# buffer.net
KiCad netlist of a schematic drawn in EAGLE
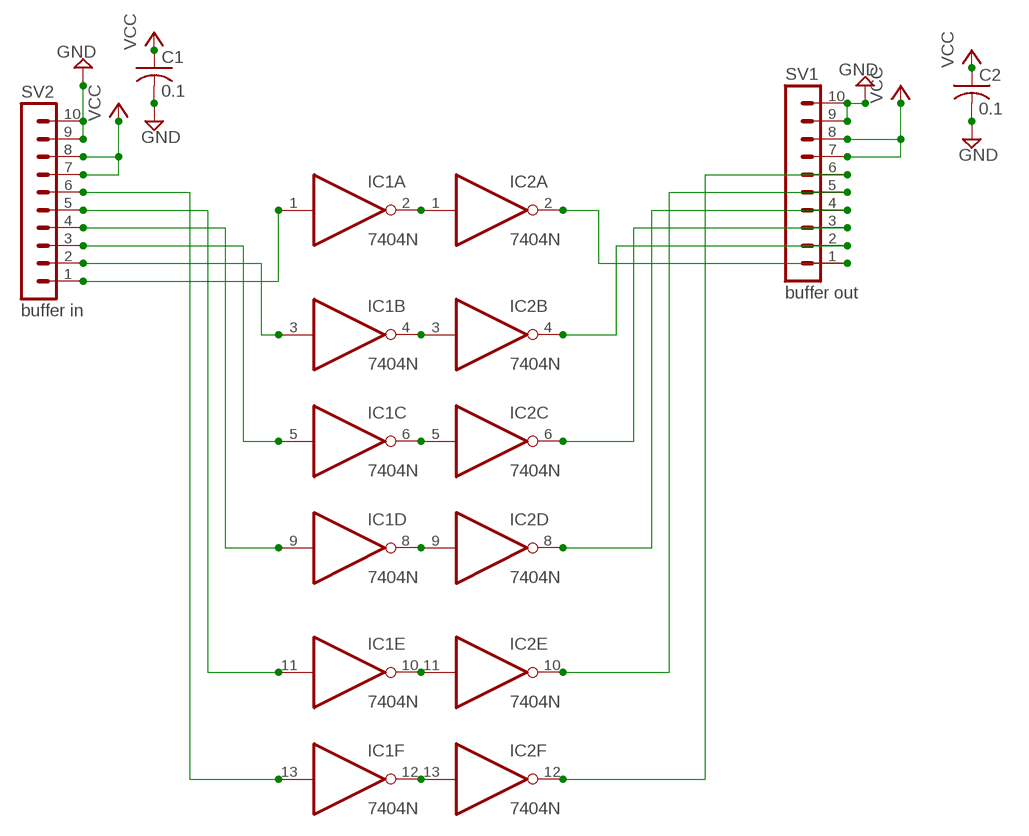
[diagram p0: schematic, sheet 1]

(export (version "E")
  (design (tool "Eeschema 10.0.6"))
  (components
    (comp (ref "C1")
      (value "0.1")
      (footprint "eagle-import:C1206")
      (libsource (lib "eagle-import") (part "C-USC1206"))
    )
    (comp (ref "C2")
      (value "0.1")
      (footprint "eagle-import:C1206")
      (libsource (lib "eagle-import") (part "C-USC1206"))
    )
    (comp (ref "IC1")
      (value "7404N")
      (footprint "eagle-import:DIL14")
      (libsource (lib "eagle-import") (part "7404N"))
    )
    (comp (ref "IC2")
      (value "7404N")
      (footprint "eagle-import:DIL14")
      (libsource (lib "eagle-import") (part "7404N"))
    )
    (comp (ref "SV1")
      (value "buffer out")
      (footprint "eagle-import:MA10-1")
      (libsource (lib "eagle-import") (part "MA10-1"))
    )
    (comp (ref "SV2")
      (value "buffer in")
      (footprint "eagle-import:MA10-1")
      (libsource (lib "eagle-import") (part "MA10-1"))
    )
  )
  (nets
    (net (code "1") (name "GND") (class "Default")
      (node (ref "C1") (pin "2") (pinfunction "2_2") (pintype "passive"))
      (node (ref "C2") (pin "2") (pinfunction "2_2") (pintype "passive"))
      (node (ref "SV1") (pin "10") (pinfunction "10_10") (pintype "passive"))
      (node (ref "SV1") (pin "9") (pinfunction "9_9") (pintype "passive"))
      (node (ref "SV2") (pin "10") (pinfunction "10_10") (pintype "passive"))
      (node (ref "SV2") (pin "9") (pinfunction "9_9") (pintype "passive"))
    )
    (net (code "2") (name "Net-(IC1A-I)") (class "Default")
      (node (ref "IC1") (pin "1") (pinfunction "I_1") (pintype "input"))
      (node (ref "SV2") (pin "1") (pinfunction "1_1") (pintype "passive"))
    )
    (net (code "3") (name "Net-(IC1A-O)") (class "Default")
      (node (ref "IC1") (pin "2") (pinfunction "O_2") (pintype "output"))
      (node (ref "IC2") (pin "1") (pinfunction "I_1") (pintype "input"))
    )
    (net (code "4") (name "Net-(IC1B-I)") (class "Default")
      (node (ref "IC1") (pin "3") (pinfunction "I_3") (pintype "input"))
      (node (ref "SV2") (pin "2") (pinfunction "2_2") (pintype "passive"))
    )
    (net (code "5") (name "Net-(IC1B-O)") (class "Default")
      (node (ref "IC1") (pin "4") (pinfunction "O_4") (pintype "output"))
      (node (ref "IC2") (pin "3") (pinfunction "I_3") (pintype "input"))
    )
    (net (code "6") (name "Net-(IC1C-I)") (class "Default")
      (node (ref "IC1") (pin "5") (pinfunction "I_5") (pintype "input"))
      (node (ref "SV2") (pin "3") (pinfunction "3_3") (pintype "passive"))
    )
    (net (code "7") (name "Net-(IC1C-O)") (class "Default")
      (node (ref "IC1") (pin "6") (pinfunction "O_6") (pintype "output"))
      (node (ref "IC2") (pin "5") (pinfunction "I_5") (pintype "input"))
    )
    (net (code "8") (name "Net-(IC1D-I)") (class "Default")
      (node (ref "IC1") (pin "9") (pinfunction "I_9") (pintype "input"))
      (node (ref "SV2") (pin "4") (pinfunction "4_4") (pintype "passive"))
    )
    (net (code "9") (name "Net-(IC1D-O)") (class "Default")
      (node (ref "IC1") (pin "8") (pinfunction "O_8") (pintype "output"))
      (node (ref "IC2") (pin "9") (pinfunction "I_9") (pintype "input"))
    )
    (net (code "10") (name "Net-(IC1E-I)") (class "Default")
      (node (ref "IC1") (pin "11") (pinfunction "I_11") (pintype "input"))
      (node (ref "SV2") (pin "5") (pinfunction "5_5") (pintype "passive"))
    )
    (net (code "11") (name "Net-(IC1E-O)") (class "Default")
      (node (ref "IC1") (pin "10") (pinfunction "O_10") (pintype "output"))
      (node (ref "IC2") (pin "11") (pinfunction "I_11") (pintype "input"))
    )
    (net (code "12") (name "Net-(IC1F-I)") (class "Default")
      (node (ref "IC1") (pin "13") (pinfunction "I_13") (pintype "input"))
      (node (ref "SV2") (pin "6") (pinfunction "6_6") (pintype "passive"))
    )
    (net (code "13") (name "Net-(IC1F-O)") (class "Default")
      (node (ref "IC1") (pin "12") (pinfunction "O_12") (pintype "output"))
      (node (ref "IC2") (pin "13") (pinfunction "I_13") (pintype "input"))
    )
    (net (code "14") (name "Net-(IC2A-O)") (class "Default")
      (node (ref "IC2") (pin "2") (pinfunction "O_2") (pintype "output"))
      (node (ref "SV1") (pin "1") (pinfunction "1_1") (pintype "passive"))
    )
    (net (code "15") (name "Net-(IC2B-O)") (class "Default")
      (node (ref "IC2") (pin "4") (pinfunction "O_4") (pintype "output"))
      (node (ref "SV1") (pin "2") (pinfunction "2_2") (pintype "passive"))
    )
    (net (code "16") (name "Net-(IC2C-O)") (class "Default")
      (node (ref "IC2") (pin "6") (pinfunction "O_6") (pintype "output"))
      (node (ref "SV1") (pin "3") (pinfunction "3_3") (pintype "passive"))
    )
    (net (code "17") (name "Net-(IC2D-O)") (class "Default")
      (node (ref "IC2") (pin "8") (pinfunction "O_8") (pintype "output"))
      (node (ref "SV1") (pin "4") (pinfunction "4_4") (pintype "passive"))
    )
    (net (code "18") (name "Net-(IC2E-O)") (class "Default")
      (node (ref "IC2") (pin "10") (pinfunction "O_10") (pintype "output"))
      (node (ref "SV1") (pin "5") (pinfunction "5_5") (pintype "passive"))
    )
    (net (code "19") (name "Net-(IC2F-O)") (class "Default")
      (node (ref "IC2") (pin "12") (pinfunction "O_12") (pintype "output"))
      (node (ref "SV1") (pin "6") (pinfunction "6_6") (pintype "passive"))
    )
    (net (code "20") (name "VCC") (class "Default")
      (node (ref "C1") (pin "1") (pinfunction "1_1") (pintype "passive"))
      (node (ref "C2") (pin "1") (pinfunction "1_1") (pintype "passive"))
      (node (ref "SV1") (pin "7") (pinfunction "7_7") (pintype "passive"))
      (node (ref "SV1") (pin "8") (pinfunction "8_8") (pintype "passive"))
      (node (ref "SV2") (pin "7") (pinfunction "7_7") (pintype "passive"))
      (node (ref "SV2") (pin "8") (pinfunction "8_8") (pintype "passive"))
    )
  )
)
